# 6switch.net
KiCad netlist of a schematic drawn in EAGLE
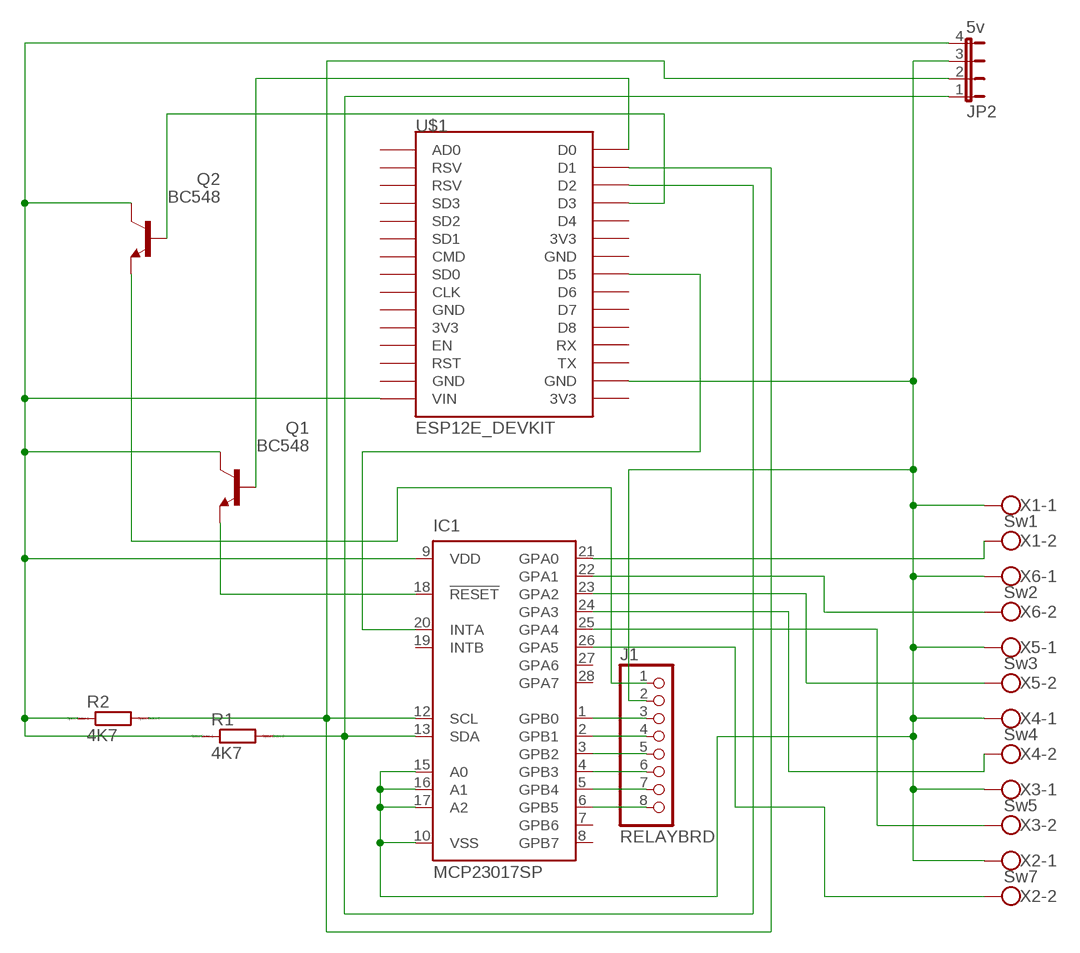
[diagram p0: schematic, sheet 1]

(export (version "E")
  (design (tool "Eeschema 10.0.6"))
  (components
    (comp (ref "IC1")
      (value "MCP23017SP")
      (footprint "eagle-import:DIL28-3")
      (fields (field (name "MF") "MICROCHIP") (field (name "MPN") "MCP23017-E/SP"))
      (libsource (lib "eagle-import") (part "MCP23017SP"))
    )
    (comp (ref "J1")
      (value "RELAYBRD")
      (footprint "eagle-import:1X08")
      (libsource (lib "eagle-import") (part "PINHD-1X8"))
    )
    (comp (ref "JP2")
      (value "5v")
      (footprint "eagle-import:JP4")
      (libsource (lib "eagle-import") (part "JP4E"))
    )
    (comp (ref "Q1")
      (value "BC548")
      (footprint "eagle-import:TO92-EBC")
      (libsource (lib "eagle-import") (part "BC548"))
    )
    (comp (ref "Q2")
      (value "BC548")
      (footprint "eagle-import:TO92-EBC")
      (libsource (lib "eagle-import") (part "BC548"))
    )
    (comp (ref "R1")
      (value "4K7")
      (footprint "eagle-import:0207_10")
      (libsource (lib "eagle-import") (part "R0207/10"))
    )
    (comp (ref "R2")
      (value "4K7")
      (footprint "eagle-import:0207_10")
      (libsource (lib "eagle-import") (part "R0207/10"))
    )
    (comp (ref "U$1")
      (value "ESP12E_DEVKIT")
      (footprint "eagle-import:ESP12E_DEVKIT")
      (libsource (lib "eagle-import") (part "ESP12E_DEVKIT"))
    )
    (comp (ref "X1")
      (value "Sw1")
      (footprint "eagle-import:W237-102")
      (fields (field (name "MPN") "237-102"))
      (libsource (lib "eagle-import") (part "W237-102"))
    )
    (comp (ref "X2")
      (value "Sw7")
      (footprint "eagle-import:W237-102")
      (fields (field (name "MPN") "237-102"))
      (libsource (lib "eagle-import") (part "W237-102"))
    )
    (comp (ref "X3")
      (value "Sw5")
      (footprint "eagle-import:W237-102")
      (fields (field (name "MPN") "237-102"))
      (libsource (lib "eagle-import") (part "W237-102"))
    )
    (comp (ref "X4")
      (value "Sw4")
      (footprint "eagle-import:W237-102")
      (fields (field (name "MPN") "237-102"))
      (libsource (lib "eagle-import") (part "W237-102"))
    )
    (comp (ref "X5")
      (value "Sw3")
      (footprint "eagle-import:W237-102")
      (fields (field (name "MPN") "237-102"))
      (libsource (lib "eagle-import") (part "W237-102"))
    )
    (comp (ref "X6")
      (value "Sw2")
      (footprint "eagle-import:W237-102")
      (fields (field (name "MPN") "237-102"))
      (libsource (lib "eagle-import") (part "W237-102"))
    )
  )
  (nets
    (net (code "1") (name "Net-(IC1-A0)") (class "Default")
      (node (ref "IC1") (pin "10") (pinfunction "VSS_10") (pintype "power_in"))
      (node (ref "IC1") (pin "15") (pinfunction "A0_15") (pintype "input"))
      (node (ref "IC1") (pin "16") (pinfunction "A1_16") (pintype "input"))
      (node (ref "IC1") (pin "17") (pinfunction "A2_17") (pintype "input"))
      (node (ref "J1") (pin "2") (pinfunction "2_2") (pintype "passive"))
      (node (ref "JP2") (pin "3") (pinfunction "3_3") (pintype "passive"))
      (node (ref "U$1") (pin "GND@3") (pinfunction "GND_GND@3") (pintype "bidirectional"))
      (node (ref "X1") (pin "1") (pinfunction "KL_1") (pintype "passive"))
      (node (ref "X2") (pin "1") (pinfunction "KL_1") (pintype "passive"))
      (node (ref "X3") (pin "1") (pinfunction "KL_1") (pintype "passive"))
      (node (ref "X4") (pin "1") (pinfunction "KL_1") (pintype "passive"))
      (node (ref "X5") (pin "1") (pinfunction "KL_1") (pintype "passive"))
      (node (ref "X6") (pin "1") (pinfunction "KL_1") (pintype "passive"))
    )
    (net (code "2") (name "Net-(IC1-GPA0)") (class "Default")
      (node (ref "IC1") (pin "21") (pinfunction "GPA0_21") (pintype "bidirectional"))
      (node (ref "X1") (pin "2") (pinfunction "KL_2") (pintype "passive"))
    )
    (net (code "3") (name "Net-(IC1-GPA1)") (class "Default")
      (node (ref "IC1") (pin "22") (pinfunction "GPA1_22") (pintype "bidirectional"))
      (node (ref "X6") (pin "2") (pinfunction "KL_2") (pintype "passive"))
    )
    (net (code "4") (name "Net-(IC1-GPA2)") (class "Default")
      (node (ref "IC1") (pin "23") (pinfunction "GPA2_23") (pintype "bidirectional"))
      (node (ref "X5") (pin "2") (pinfunction "KL_2") (pintype "passive"))
    )
    (net (code "5") (name "Net-(IC1-GPA3)") (class "Default")
      (node (ref "IC1") (pin "24") (pinfunction "GPA3_24") (pintype "bidirectional"))
      (node (ref "X4") (pin "2") (pinfunction "KL_2") (pintype "passive"))
    )
    (net (code "6") (name "Net-(IC1-GPA4)") (class "Default")
      (node (ref "IC1") (pin "25") (pinfunction "GPA4_25") (pintype "bidirectional"))
      (node (ref "X3") (pin "2") (pinfunction "KL_2") (pintype "passive"))
    )
    (net (code "7") (name "Net-(IC1-GPA5)") (class "Default")
      (node (ref "IC1") (pin "26") (pinfunction "GPA5_26") (pintype "bidirectional"))
      (node (ref "X2") (pin "2") (pinfunction "KL_2") (pintype "passive"))
    )
    (net (code "8") (name "Net-(IC1-GPB0)") (class "Default")
      (node (ref "IC1") (pin "1") (pinfunction "GPB0_1") (pintype "bidirectional"))
      (node (ref "J1") (pin "3") (pinfunction "3_3") (pintype "passive"))
    )
    (net (code "9") (name "Net-(IC1-GPB1)") (class "Default")
      (node (ref "IC1") (pin "2") (pinfunction "GPB1_2") (pintype "bidirectional"))
      (node (ref "J1") (pin "4") (pinfunction "4_4") (pintype "passive"))
    )
    (net (code "10") (name "Net-(IC1-GPB2)") (class "Default")
      (node (ref "IC1") (pin "3") (pinfunction "GPB2_3") (pintype "bidirectional"))
      (node (ref "J1") (pin "5") (pinfunction "5_5") (pintype "passive"))
    )
    (net (code "11") (name "Net-(IC1-GPB3)") (class "Default")
      (node (ref "IC1") (pin "4") (pinfunction "GPB3_4") (pintype "bidirectional"))
      (node (ref "J1") (pin "6") (pinfunction "6_6") (pintype "passive"))
    )
    (net (code "12") (name "Net-(IC1-GPB4)") (class "Default")
      (node (ref "IC1") (pin "5") (pinfunction "GPB4_5") (pintype "bidirectional"))
      (node (ref "J1") (pin "7") (pinfunction "7_7") (pintype "passive"))
    )
    (net (code "13") (name "Net-(IC1-GPB5)") (class "Default")
      (node (ref "IC1") (pin "6") (pinfunction "GPB5_6") (pintype "bidirectional"))
      (node (ref "J1") (pin "8") (pinfunction "8_8") (pintype "passive"))
    )
    (net (code "14") (name "Net-(IC1-INTA)") (class "Default")
      (node (ref "IC1") (pin "20") (pinfunction "INTA_20") (pintype "output"))
      (node (ref "U$1") (pin "D5") (pinfunction "D5_D5") (pintype "bidirectional"))
    )
    (net (code "15") (name "Net-(IC1-SCL)") (class "Default")
      (node (ref "IC1") (pin "12") (pinfunction "SCL_12") (pintype "input"))
      (node (ref "JP2") (pin "2") (pinfunction "2_2") (pintype "passive"))
      (node (ref "R2") (pin "2") (pinfunction "2_2") (pintype "passive"))
      (node (ref "U$1") (pin "D1") (pinfunction "D1_D1") (pintype "bidirectional"))
    )
    (net (code "16") (name "Net-(IC1-SDA)") (class "Default")
      (node (ref "IC1") (pin "13") (pinfunction "SDA_13") (pintype "bidirectional"))
      (node (ref "JP2") (pin "1") (pinfunction "1_1") (pintype "passive"))
      (node (ref "R1") (pin "2") (pinfunction "2_2") (pintype "passive"))
      (node (ref "U$1") (pin "D2") (pinfunction "D2_D2") (pintype "bidirectional"))
    )
    (net (code "17") (name "Net-(IC1-VDD)") (class "Default")
      (node (ref "IC1") (pin "9") (pinfunction "VDD_9") (pintype "power_in"))
      (node (ref "JP2") (pin "4") (pinfunction "4_4") (pintype "passive"))
      (node (ref "Q1") (pin "C") (pinfunction "C_C") (pintype "passive"))
      (node (ref "Q2") (pin "C") (pinfunction "C_C") (pintype "passive"))
      (node (ref "R1") (pin "1") (pinfunction "1_1") (pintype "passive"))
      (node (ref "R2") (pin "1") (pinfunction "1_1") (pintype "passive"))
      (node (ref "U$1") (pin "VIN") (pinfunction "VIN_VIN") (pintype "bidirectional"))
    )
    (net (code "18") (name "Net-(IC1-~{RESET})") (class "Default")
      (node (ref "IC1") (pin "18") (pinfunction "~{RESET}_18") (pintype "input"))
      (node (ref "Q1") (pin "E") (pinfunction "E_E") (pintype "passive"))
    )
    (net (code "19") (name "Net-(J1-Pad1)") (class "Default")
      (node (ref "J1") (pin "1") (pinfunction "1_1") (pintype "passive"))
      (node (ref "Q2") (pin "E") (pinfunction "E_E") (pintype "passive"))
    )
    (net (code "20") (name "Net-(Q1-PadB)") (class "Default")
      (node (ref "Q1") (pin "B") (pinfunction "B_B") (pintype "passive"))
      (node (ref "U$1") (pin "D0") (pinfunction "D0_D0") (pintype "bidirectional"))
    )
    (net (code "21") (name "Net-(Q2-PadB)") (class "Default")
      (node (ref "Q2") (pin "B") (pinfunction "B_B") (pintype "passive"))
      (node (ref "U$1") (pin "D3") (pinfunction "D3_D3") (pintype "bidirectional"))
    )
    (net (code "22") (name "unconnected-(IC1-GPA6-Pad27)") (class "Default")
      (node (ref "IC1") (pin "27") (pinfunction "GPA6_27") (pintype "bidirectional"))
    )
    (net (code "23") (name "unconnected-(IC1-GPA7-Pad28)") (class "Default")
      (node (ref "IC1") (pin "28") (pinfunction "GPA7_28") (pintype "bidirectional"))
    )
    (net (code "24") (name "unconnected-(IC1-GPB6-Pad7)") (class "Default")
      (node (ref "IC1") (pin "7") (pinfunction "GPB6_7") (pintype "bidirectional"))
    )
    (net (code "25") (name "unconnected-(IC1-GPB7-Pad8)") (class "Default")
      (node (ref "IC1") (pin "8") (pinfunction "GPB7_8") (pintype "bidirectional"))
    )
    (net (code "26") (name "unconnected-(IC1-INTB-Pad19)") (class "Default")
      (node (ref "IC1") (pin "19") (pinfunction "INTB_19") (pintype "output"))
    )
    (net (code "27") (name "unconnected-(U$1-3V3-Pad3V3@0)") (class "Default")
      (node (ref "U$1") (pin "3V3@0") (pinfunction "3V3_3V3@0") (pintype "bidirectional"))
    )
    (net (code "28") (name "unconnected-(U$1-3V3-Pad3V3@1)") (class "Default")
      (node (ref "U$1") (pin "3V3@1") (pinfunction "3V3_3V3@1") (pintype "bidirectional"))
    )
    (net (code "29") (name "unconnected-(U$1-3V3-Pad3V3@2)") (class "Default")
      (node (ref "U$1") (pin "3V3@2") (pinfunction "3V3_3V3@2") (pintype "bidirectional"))
    )
    (net (code "30") (name "unconnected-(U$1-GND-PadGND@0)") (class "Default")
      (node (ref "U$1") (pin "GND@0") (pinfunction "GND_GND@0") (pintype "bidirectional"))
    )
    (net (code "31") (name "unconnected-(U$1-GND-PadGND@1)") (class "Default")
      (node (ref "U$1") (pin "GND@1") (pinfunction "GND_GND@1") (pintype "bidirectional"))
    )
    (net (code "32") (name "unconnected-(U$1-GND-PadGND@2)") (class "Default")
      (node (ref "U$1") (pin "GND@2") (pinfunction "GND_GND@2") (pintype "bidirectional"))
    )
    (net (code "33") (name "unconnected-(U$1-PadAD0)") (class "Default")
      (node (ref "U$1") (pin "AD0") (pinfunction "AD0_AD0") (pintype "bidirectional"))
    )
    (net (code "34") (name "unconnected-(U$1-PadCLK)") (class "Default")
      (node (ref "U$1") (pin "CLK") (pinfunction "CLK_CLK") (pintype "bidirectional"))
    )
    (net (code "35") (name "unconnected-(U$1-PadCMD)") (class "Default")
      (node (ref "U$1") (pin "CMD") (pinfunction "CMD_CMD") (pintype "bidirectional"))
    )
    (net (code "36") (name "unconnected-(U$1-PadD4)") (class "Default")
      (node (ref "U$1") (pin "D4") (pinfunction "D4_D4") (pintype "bidirectional"))
    )
    (net (code "37") (name "unconnected-(U$1-PadD6)") (class "Default")
      (node (ref "U$1") (pin "D6") (pinfunction "D6_D6") (pintype "bidirectional"))
    )
    (net (code "38") (name "unconnected-(U$1-PadD7)") (class "Default")
      (node (ref "U$1") (pin "D7") (pinfunction "D7_D7") (pintype "bidirectional"))
    )
    (net (code "39") (name "unconnected-(U$1-PadD8)") (class "Default")
      (node (ref "U$1") (pin "D8") (pinfunction "D8_D8") (pintype "bidirectional"))
    )
    (net (code "40") (name "unconnected-(U$1-PadEN)") (class "Default")
      (node (ref "U$1") (pin "EN") (pinfunction "EN_EN") (pintype "bidirectional"))
    )
    (net (code "41") (name "unconnected-(U$1-PadRST)") (class "Default")
      (node (ref "U$1") (pin "RST") (pinfunction "RST_RST") (pintype "bidirectional"))
    )
    (net (code "42") (name "unconnected-(U$1-PadRX)") (class "Default")
      (node (ref "U$1") (pin "RX") (pinfunction "RX_RX") (pintype "bidirectional"))
    )
    (net (code "43") (name "unconnected-(U$1-PadSD0)") (class "Default")
      (node (ref "U$1") (pin "SD0") (pinfunction "SD0_SD0") (pintype "bidirectional"))
    )
    (net (code "44") (name "unconnected-(U$1-PadSD1)") (class "Default")
      (node (ref "U$1") (pin "SD1") (pinfunction "SD1_SD1") (pintype "bidirectional"))
    )
    (net (code "45") (name "unconnected-(U$1-PadSD2)") (class "Default")
      (node (ref "U$1") (pin "SD2") (pinfunction "SD2_SD2") (pintype "bidirectional"))
    )
    (net (code "46") (name "unconnected-(U$1-PadSD3)") (class "Default")
      (node (ref "U$1") (pin "SD3") (pinfunction "SD3_SD3") (pintype "bidirectional"))
    )
    (net (code "47") (name "unconnected-(U$1-PadTX)") (class "Default")
      (node (ref "U$1") (pin "TX") (pinfunction "TX_TX") (pintype "bidirectional"))
    )
    (net (code "48") (name "unconnected-(U$1-RSV-PadRSV@0)") (class "Default")
      (node (ref "U$1") (pin "RSV@0") (pinfunction "RSV_RSV@0") (pintype "bidirectional"))
    )
    (net (code "49") (name "unconnected-(U$1-RSV-PadRSV@1)") (class "Default")
      (node (ref "U$1") (pin "RSV@1") (pinfunction "RSV_RSV@1") (pintype "bidirectional"))
    )
  )
)
